# MCU.net
KiCad netlist of a schematic drawn in Altium Designer
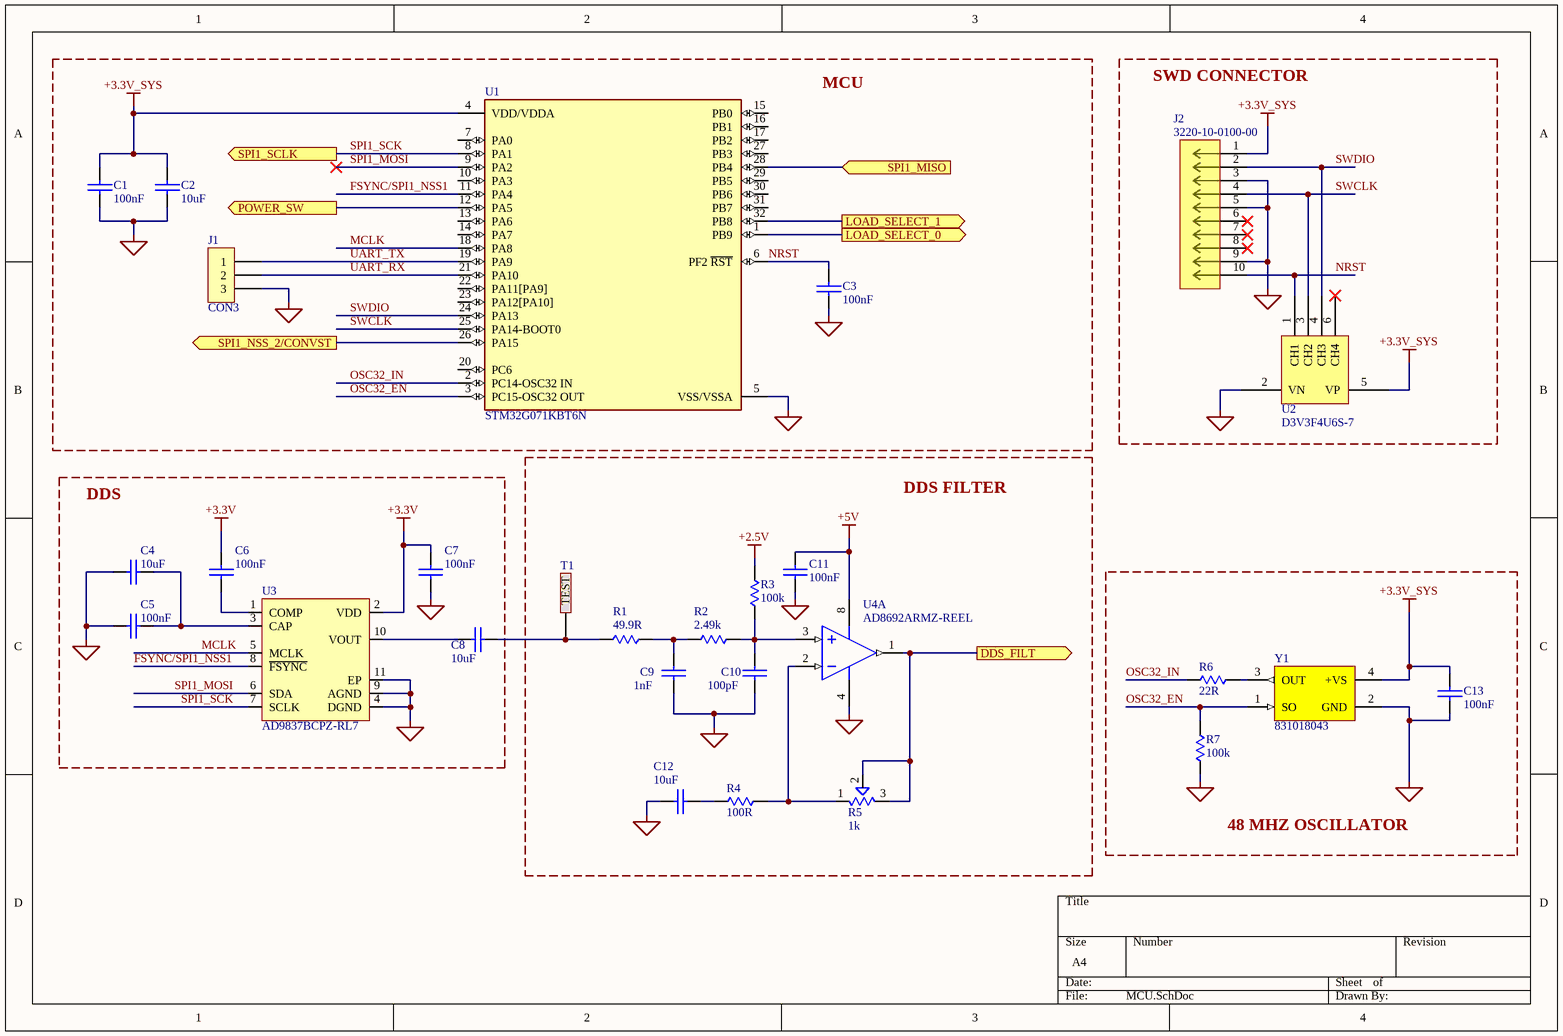
[diagram p0: MCU.SchDoc]

(export (version "E")
  (design (tool "Eeschema 10.0.6"))
  (components
    (comp (ref "C1")
      (value "100nF")
      (footprint "0603-CAP")
      (description "CAP CER 100 NF 50V X7R 0603")
      (libsource (lib "SGL_Capacitors") (part "Capacitor"))
    )
    (comp (ref "C2")
      (value "10uF")
      (footprint "0603-CAP")
      (description "CAP CER 10uF 6.3V X5R 0603")
      (libsource (lib "SGL_Capacitors") (part "Capacitor"))
    )
    (comp (ref "C3")
      (value "100nF")
      (footprint "0603-CAP")
      (description "CAP CER 100 NF 50V X7R 0603")
      (libsource (lib "SGL_Capacitors") (part "Capacitor"))
    )
    (comp (ref "C4")
      (value "10uF")
      (footprint "0603-CAP")
      (description "CAP CER 10uF 6.3V X5R 0603")
      (libsource (lib "SGL_Capacitors") (part "Capacitor"))
    )
    (comp (ref "C5")
      (value "100nF")
      (footprint "0603-CAP")
      (description "CAP CER 100 NF 50V X7R 0603")
      (libsource (lib "SGL_Capacitors") (part "Capacitor"))
    )
    (comp (ref "C6")
      (value "100nF")
      (footprint "0603-CAP")
      (description "CAP CER 100 NF 50V X7R 0603")
      (libsource (lib "SGL_Capacitors") (part "Capacitor"))
    )
    (comp (ref "C7")
      (value "100nF")
      (footprint "0603-CAP")
      (description "CAP CER 100 NF 50V X7R 0603")
      (libsource (lib "SGL_Capacitors") (part "Capacitor"))
    )
    (comp (ref "C8")
      (value "10uF")
      (footprint "0603-CAP")
      (description "CAP CER 10uF 6.3V X5R 0603")
      (libsource (lib "SGL_Capacitors") (part "Capacitor"))
    )
    (comp (ref "C9")
      (value "1nF")
      (footprint "0603-CAP")
      (description "CAP CER 1000 PF 50V C0G 0603")
      (libsource (lib "SGL_Capacitors") (part "Capacitor"))
    )
    (comp (ref "C10")
      (value "100pF")
      (footprint "0603-CAP")
      (description "CAP CER 100 PF 50V C0G 0603")
      (libsource (lib "SGL_Capacitors") (part "Capacitor"))
    )
    (comp (ref "C11")
      (value "100nF")
      (footprint "0603-CAP")
      (description "CAP CER 100 NF 50V X7R 0603")
      (libsource (lib "SGL_Capacitors") (part "Capacitor"))
    )
    (comp (ref "C12")
      (value "10uF")
      (footprint "0603-CAP")
      (description "CAP CER 10uF 6.3V X5R 0603")
      (libsource (lib "SGL_Capacitors") (part "Capacitor"))
    )
    (comp (ref "C13")
      (value "100nF")
      (footprint "0603-CAP")
      (description "CAP CER 100 NF 50V X7R 0603")
      (libsource (lib "SGL_Capacitors") (part "Capacitor"))
    )
    (comp (ref "J1")
      (value "CON3")
      (footprint "SIP3")
      (description "Connector")
      (libsource (lib "BioZ") (part "CON3"))
    )
    (comp (ref "J2")
      (value "3220-10-0100-00")
      (footprint "CONN_3220-10-0100-00_CNC")
      (description "Description")
      (fields (field (name "COPYRIGHT") "Copyright (C) 2025 Ultra Librarian. All rights reserved."))
      (libsource (lib "BioZ") (part "3220-10-0100-00"))
    )
    (comp (ref "R1")
      (value "49.9R")
      (footprint "0603-RES")
      (description "RES SMD 49.9OHM 0.1% 1/10W 0603")
      (libsource (lib "SGL_Resistives") (part "RESISTOR"))
    )
    (comp (ref "R2")
      (value "2.49k")
      (footprint "0603-RES")
      (description "RES SMD 2.49kOHM 0.1% 1/10W 0603")
      (libsource (lib "SGL_Resistives") (part "RESISTOR"))
    )
    (comp (ref "R3")
      (value "100k")
      (footprint "0603-RES")
      (description "RES SMD 100KOHM 0.1% 1/10W 0603")
      (libsource (lib "SGL_Resistives") (part "RESISTOR"))
    )
    (comp (ref "R4")
      (value "100R")
      (footprint "0603-RES")
      (description "RES SMD 100OHM 0.1% 1/10W 0603")
      (libsource (lib "SGL_Resistives") (part "RESISTOR"))
    )
    (comp (ref "R5")
      (value "1k")
      (footprint "TRIM_PVG5A102C03R00")
      (description "TRIMMER-SMD 4MM SQ MT CERMET Square / 12 turn / Sealed ¦ Bourns PVG5A102C03R00")
      (fields (field (name "MF") "Bourns") (field (name "MP") "PVG5A102C03R00"))
      (libsource (lib "BioZ") (part "PVG5A102C03R00"))
    )
    (comp (ref "R6")
      (value "22R")
      (footprint "0603-RES")
      (description "RES SMD 22OHM 0.1% 1/10W 0603")
      (libsource (lib "SGL_Resistives") (part "RESISTOR"))
    )
    (comp (ref "R7")
      (value "100k")
      (footprint "0603-RES")
      (description "RES SMD 100KOHM 0.1% 1/10W 0603")
      (libsource (lib "SGL_Resistives") (part "RESISTOR"))
    )
    (comp (ref "T1")
      (value "5002K")
      (footprint "TESTPOINT White")
      (description "PC TEST POINT MINIATURE WHITE")
      (libsource (lib "SGL_Connectors") (part "Testpoint white"))
    )
    (comp (ref "U1")
      (value "STM32G071KBT6N")
      (footprint "FP-LQFP32-5V-IPC_C")
      (description "IC MCU 32BIT 128KB FLASH 32LQFP")
      (libsource (lib "Altium Content Vault") (part "9b54295ea68006ce9760e395ce3e3f0"))
    )
    (comp (ref "U2")
      (value "D3V3F4U6S-7")
      (footprint "SOT-363_DIO")
      (description "Description")
      (fields (field (name "COPYRIGHT") "Copyright (C) 2025 Ultra Librarian. All rights reserved."))
      (libsource (lib "BioZ") (part "D3V3F4U6S-7"))
    )
    (comp (ref "U3")
      (value "AD9837BCPZ-RL7")
      (footprint "LFCSP-WD (3x3) - 10 Pin EPAD")
      (description "Direct Digital Synthesis IC 10 b 16 MHz 28 b Tuning 10-LFCSP-WD (3x3)")
      (libsource (lib "BioZ") (part "AD9837BCPZ-RL7"))
    )
    (comp (ref "U4")
      (value "AD8692ARMZ-REEL")
      (footprint "ADI-RM-8_M")
      (fields (field (name "MANUFACTURER") "Analog Devices") (field (name "GENERIC PART NUMBER") "AD8692"))
      (libsource (lib "Altium Content Vault") (part "ADI-ADA4000-2-X-8"))
    )
    (comp (ref "Y1")
      (value "831018043")
      (footprint "WE-SPXO_CFPS-73")
      (fields (field (name "MF") "{'manufacturer': u'~{W}xfcrth Elektronik'}"))
      (libsource (lib "BioZ") (part "WE-SPXO_CFPS-73"))
    )
  )
  (nets
    (net (code "1") (name "+2.5V") (class "Default")
      (node (ref "R3") (pin "2") (pinfunction "2_2") (pintype "passive"))
    )
    (net (code "2") (name "+3.3V") (class "Default")
      (node (ref "C6") (pin "1") (pinfunction "1_1") (pintype "passive"))
      (node (ref "C7") (pin "1") (pinfunction "1_1") (pintype "passive"))
      (node (ref "U3") (pin "2") (pinfunction "VDD_2") (pintype "passive"))
    )
    (net (code "3") (name "+3.3V_SYS") (class "Default")
      (node (ref "C1") (pin "2") (pinfunction "2_2") (pintype "passive"))
      (node (ref "C13") (pin "2") (pinfunction "2_2") (pintype "passive"))
      (node (ref "C2") (pin "1") (pinfunction "1_1") (pintype "passive"))
      (node (ref "J2") (pin "1") (pinfunction "1_1") (pintype "passive"))
      (node (ref "U1") (pin "4") (pinfunction "VDD/VDDA_4") (pintype "power_in"))
      (node (ref "U2") (pin "5") (pinfunction "VP_5") (pintype "power_in"))
      (node (ref "Y1") (pin "4") (pinfunction "+VS_4") (pintype "power_in"))
    )
    (net (code "4") (name "+5V") (class "Default")
      (node (ref "C11") (pin "1") (pinfunction "1_1") (pintype "passive"))
      (node (ref "U4") (pin "8") (pinfunction "+V_8") (pintype "power_in"))
    )
    (net (code "5") (name "/DDS_FILT") (class "Default")
      (node (ref "R5") (pin "2") (pinfunction "2_2") (pintype "passive"))
      (node (ref "R5") (pin "3") (pinfunction "3_3") (pintype "passive"))
      (node (ref "U4") (pin "1") (pinfunction "OUT_A_1") (pintype "output"))
    )
    (net (code "6") (name "/FSYNC{slash}SPI1_NSS1") (class "Default")
      (node (ref "U1") (pin "11") (pinfunction "PA4_11") (pintype "bidirectional"))
      (node (ref "U3") (pin "8") (pinfunction "~{FSYNC}_8") (pintype "passive"))
    )
    (net (code "7") (name "/LOAD_SELECT_0") (class "Default")
      (node (ref "U1") (pin "1") (pinfunction "PB9_1") (pintype "bidirectional"))
    )
    (net (code "8") (name "/LOAD_SELECT_1") (class "Default")
      (node (ref "U1") (pin "32") (pinfunction "PB8_32") (pintype "bidirectional"))
    )
    (net (code "9") (name "/MCLK") (class "Default")
      (node (ref "U1") (pin "18") (pinfunction "PA8_18") (pintype "bidirectional"))
      (node (ref "U3") (pin "5") (pinfunction "MCLK_5") (pintype "passive"))
    )
    (net (code "10") (name "/NRST") (class "Default")
      (node (ref "C3") (pin "2") (pinfunction "2_2") (pintype "passive"))
      (node (ref "J2") (pin "10") (pinfunction "10_10") (pintype "passive"))
      (node (ref "U1") (pin "6") (pinfunction "PF2_~{RST}_6") (pintype "bidirectional"))
      (node (ref "U2") (pin "1") (pinfunction "CH1_1") (pintype "passive"))
    )
    (net (code "11") (name "/OSC32_EN") (class "Default")
      (node (ref "R7") (pin "2") (pinfunction "2_2") (pintype "passive"))
      (node (ref "U1") (pin "3") (pinfunction "PC15-OSC32_OUT_3") (pintype "bidirectional"))
      (node (ref "Y1") (pin "1") (pinfunction "SO_1") (pintype "input"))
    )
    (net (code "12") (name "/OSC32_IN") (class "Default")
      (node (ref "R6") (pin "1") (pinfunction "1_1") (pintype "passive"))
      (node (ref "U1") (pin "2") (pinfunction "PC14-OSC32_IN_2") (pintype "bidirectional"))
    )
    (net (code "13") (name "/POWER_SW") (class "Default")
      (node (ref "U1") (pin "12") (pinfunction "PA5_12") (pintype "bidirectional"))
    )
    (net (code "14") (name "/SPI1_MISO") (class "Default")
      (node (ref "U1") (pin "28") (pinfunction "PB4_28") (pintype "bidirectional"))
    )
    (net (code "15") (name "/SPI1_MOSI") (class "Default")
      (node (ref "U1") (pin "9") (pinfunction "PA2_9") (pintype "bidirectional"))
      (node (ref "U3") (pin "6") (pinfunction "SDA_6") (pintype "passive"))
    )
    (net (code "16") (name "/SPI1_NSS_2{slash}CONVST") (class "Default")
      (node (ref "U1") (pin "26") (pinfunction "PA15_26") (pintype "bidirectional"))
    )
    (net (code "17") (name "/SPI1_SCK") (class "Default")
      (node (ref "U1") (pin "8") (pinfunction "PA1_8") (pintype "bidirectional"))
      (node (ref "U3") (pin "7") (pinfunction "SCLK_7") (pintype "passive"))
    )
    (net (code "18") (name "/SWCLK") (class "Default")
      (node (ref "J2") (pin "4") (pinfunction "4_4") (pintype "passive"))
      (node (ref "U1") (pin "25") (pinfunction "PA14-BOOT0_25") (pintype "bidirectional"))
      (node (ref "U2") (pin "3") (pinfunction "CH2_3") (pintype "passive"))
    )
    (net (code "19") (name "/SWDIO") (class "Default")
      (node (ref "J2") (pin "2") (pinfunction "2_2") (pintype "passive"))
      (node (ref "U1") (pin "24") (pinfunction "PA13_24") (pintype "bidirectional"))
      (node (ref "U2") (pin "4") (pinfunction "CH3_4") (pintype "passive"))
    )
    (net (code "20") (name "/UART_RX") (class "Default")
      (node (ref "J1") (pin "2") (pinfunction "2_2") (pintype "passive"))
      (node (ref "U1") (pin "21") (pinfunction "PA10_21") (pintype "bidirectional"))
    )
    (net (code "21") (name "/UART_TX") (class "Default")
      (node (ref "J1") (pin "1") (pinfunction "1_1") (pintype "passive"))
      (node (ref "U1") (pin "19") (pinfunction "PA9_19") (pintype "bidirectional"))
    )
    (net (code "22") (name "GND") (class "Default")
      (node (ref "C1") (pin "1") (pinfunction "1_1") (pintype "passive"))
      (node (ref "C10") (pin "2") (pinfunction "2_2") (pintype "passive"))
      (node (ref "C11") (pin "2") (pinfunction "2_2") (pintype "passive"))
      (node (ref "C12") (pin "2") (pinfunction "2_2") (pintype "passive"))
      (node (ref "C13") (pin "1") (pinfunction "1_1") (pintype "passive"))
      (node (ref "C2") (pin "2") (pinfunction "2_2") (pintype "passive"))
      (node (ref "C3") (pin "1") (pinfunction "1_1") (pintype "passive"))
      (node (ref "C4") (pin "2") (pinfunction "2_2") (pintype "passive"))
      (node (ref "C5") (pin "2") (pinfunction "2_2") (pintype "passive"))
      (node (ref "C7") (pin "2") (pinfunction "2_2") (pintype "passive"))
      (node (ref "C9") (pin "2") (pinfunction "2_2") (pintype "passive"))
      (node (ref "J1") (pin "3") (pinfunction "3_3") (pintype "passive"))
      (node (ref "J2") (pin "3") (pinfunction "3_3") (pintype "passive"))
      (node (ref "J2") (pin "5") (pinfunction "5_5") (pintype "passive"))
      (node (ref "J2") (pin "9") (pinfunction "9_9") (pintype "passive"))
      (node (ref "R7") (pin "1") (pinfunction "1_1") (pintype "passive"))
      (node (ref "U1") (pin "5") (pinfunction "VSS/VSSA_5") (pintype "power_in"))
      (node (ref "U2") (pin "2") (pinfunction "VN_2") (pintype "power_in"))
      (node (ref "U3") (pin "11") (pinfunction "EP_11") (pintype "passive"))
      (node (ref "U3") (pin "4") (pinfunction "DGND_4") (pintype "passive"))
      (node (ref "U3") (pin "9") (pinfunction "AGND_9") (pintype "passive"))
      (node (ref "U4") (pin "4") (pinfunction "-V_4") (pintype "power_in"))
      (node (ref "Y1") (pin "2") (pinfunction "GND_2") (pintype "power_in"))
    )
    (net (code "23") (name "Net-(C9-Pad1)") (class "Default")
      (node (ref "C9") (pin "1") (pinfunction "1_1") (pintype "passive"))
      (node (ref "R1") (pin "2") (pinfunction "2_2") (pintype "passive"))
      (node (ref "R2") (pin "1") (pinfunction "1_1") (pintype "passive"))
    )
    (net (code "24") (name "Net-(C12-Pad1)") (class "Default")
      (node (ref "C12") (pin "1") (pinfunction "1_1") (pintype "passive"))
      (node (ref "R4") (pin "1") (pinfunction "1_1") (pintype "passive"))
    )
    (net (code "25") (name "Net-(T1-TEST)") (class "Default")
      (node (ref "C8") (pin "1") (pinfunction "1_1") (pintype "passive"))
      (node (ref "R1") (pin "1") (pinfunction "1_1") (pintype "passive"))
      (node (ref "T1") (pin "1") (pinfunction "TEST_1") (pintype "passive"))
    )
    (net (code "26") (name "Net-(U3-CAP)") (class "Default")
      (node (ref "C4") (pin "1") (pinfunction "1_1") (pintype "passive"))
      (node (ref "C5") (pin "1") (pinfunction "1_1") (pintype "passive"))
      (node (ref "U3") (pin "3") (pinfunction "CAP_3") (pintype "passive"))
    )
    (net (code "27") (name "Net-(U3-COMP)") (class "Default")
      (node (ref "C6") (pin "2") (pinfunction "2_2") (pintype "passive"))
      (node (ref "U3") (pin "1") (pinfunction "COMP_1") (pintype "passive"))
    )
    (net (code "28") (name "Net-(U3-VOUT)") (class "Default")
      (node (ref "C8") (pin "2") (pinfunction "2_2") (pintype "passive"))
      (node (ref "U3") (pin "10") (pinfunction "VOUT_10") (pintype "passive"))
    )
    (net (code "29") (name "Net-(U4A-+IN_A)") (class "Default")
      (node (ref "C10") (pin "1") (pinfunction "1_1") (pintype "passive"))
      (node (ref "R2") (pin "2") (pinfunction "2_2") (pintype "passive"))
      (node (ref "R3") (pin "1") (pinfunction "1_1") (pintype "passive"))
      (node (ref "U4") (pin "3") (pinfunction "+IN_A_3") (pintype "input"))
    )
    (net (code "30") (name "Net-(U4A--IN_A)") (class "Default")
      (node (ref "R4") (pin "2") (pinfunction "2_2") (pintype "passive"))
      (node (ref "R5") (pin "1") (pinfunction "1_1") (pintype "passive"))
      (node (ref "U4") (pin "2") (pinfunction "-IN_A_2") (pintype "input"))
    )
    (net (code "31") (name "Net-(Y1-OUT)") (class "Default")
      (node (ref "R6") (pin "2") (pinfunction "2_2") (pintype "passive"))
      (node (ref "Y1") (pin "3") (pinfunction "OUT_3") (pintype "output"))
    )
    (net (code "32") (name "unconnected-(J2-Pad6)") (class "Default")
      (node (ref "J2") (pin "6") (pinfunction "6_6") (pintype "passive+no_connect"))
    )
    (net (code "33") (name "unconnected-(J2-Pad7)") (class "Default")
      (node (ref "J2") (pin "7") (pinfunction "7_7") (pintype "passive+no_connect"))
    )
    (net (code "34") (name "unconnected-(J2-Pad8)") (class "Default")
      (node (ref "J2") (pin "8") (pinfunction "8_8") (pintype "passive+no_connect"))
    )
    (net (code "35") (name "unconnected-(U1-PA0-Pad7)") (class "Default")
      (node (ref "U1") (pin "7") (pinfunction "PA0_7") (pintype "bidirectional"))
    )
    (net (code "36") (name "unconnected-(U1-PA3-Pad10)") (class "Default")
      (node (ref "U1") (pin "10") (pinfunction "PA3_10") (pintype "bidirectional"))
    )
    (net (code "37") (name "unconnected-(U1-PA6-Pad13)") (class "Default")
      (node (ref "U1") (pin "13") (pinfunction "PA6_13") (pintype "bidirectional"))
    )
    (net (code "38") (name "unconnected-(U1-PA7-Pad14)") (class "Default")
      (node (ref "U1") (pin "14") (pinfunction "PA7_14") (pintype "bidirectional"))
    )
    (net (code "39") (name "unconnected-(U1-PA11[PA9]-Pad22)") (class "Default")
      (node (ref "U1") (pin "22") (pinfunction "PA11[PA9]_22") (pintype "bidirectional"))
    )
    (net (code "40") (name "unconnected-(U1-PA12[PA10]-Pad23)") (class "Default")
      (node (ref "U1") (pin "23") (pinfunction "PA12[PA10]_23") (pintype "bidirectional"))
    )
    (net (code "41") (name "unconnected-(U1-PB0-Pad15)") (class "Default")
      (node (ref "U1") (pin "15") (pinfunction "PB0_15") (pintype "bidirectional"))
    )
    (net (code "42") (name "unconnected-(U1-PB1-Pad16)") (class "Default")
      (node (ref "U1") (pin "16") (pinfunction "PB1_16") (pintype "bidirectional"))
    )
    (net (code "43") (name "unconnected-(U1-PB2-Pad17)") (class "Default")
      (node (ref "U1") (pin "17") (pinfunction "PB2_17") (pintype "bidirectional"))
    )
    (net (code "44") (name "unconnected-(U1-PB3-Pad27)") (class "Default")
      (node (ref "U1") (pin "27") (pinfunction "PB3_27") (pintype "bidirectional"))
    )
    (net (code "45") (name "unconnected-(U1-PB5-Pad29)") (class "Default")
      (node (ref "U1") (pin "29") (pinfunction "PB5_29") (pintype "bidirectional"))
    )
    (net (code "46") (name "unconnected-(U1-PB6-Pad30)") (class "Default")
      (node (ref "U1") (pin "30") (pinfunction "PB6_30") (pintype "bidirectional"))
    )
    (net (code "47") (name "unconnected-(U1-PB7-Pad31)") (class "Default")
      (node (ref "U1") (pin "31") (pinfunction "PB7_31") (pintype "bidirectional"))
    )
    (net (code "48") (name "unconnected-(U1-PC6-Pad20)") (class "Default")
      (node (ref "U1") (pin "20") (pinfunction "PC6_20") (pintype "bidirectional"))
    )
    (net (code "49") (name "unconnected-(U2-CH4-Pad6)") (class "Default")
      (node (ref "U2") (pin "6") (pinfunction "CH4_6") (pintype "passive+no_connect"))
    )
  )
)
